# Atmega328P.net
KiCad netlist of a schematic drawn in Altium Designer
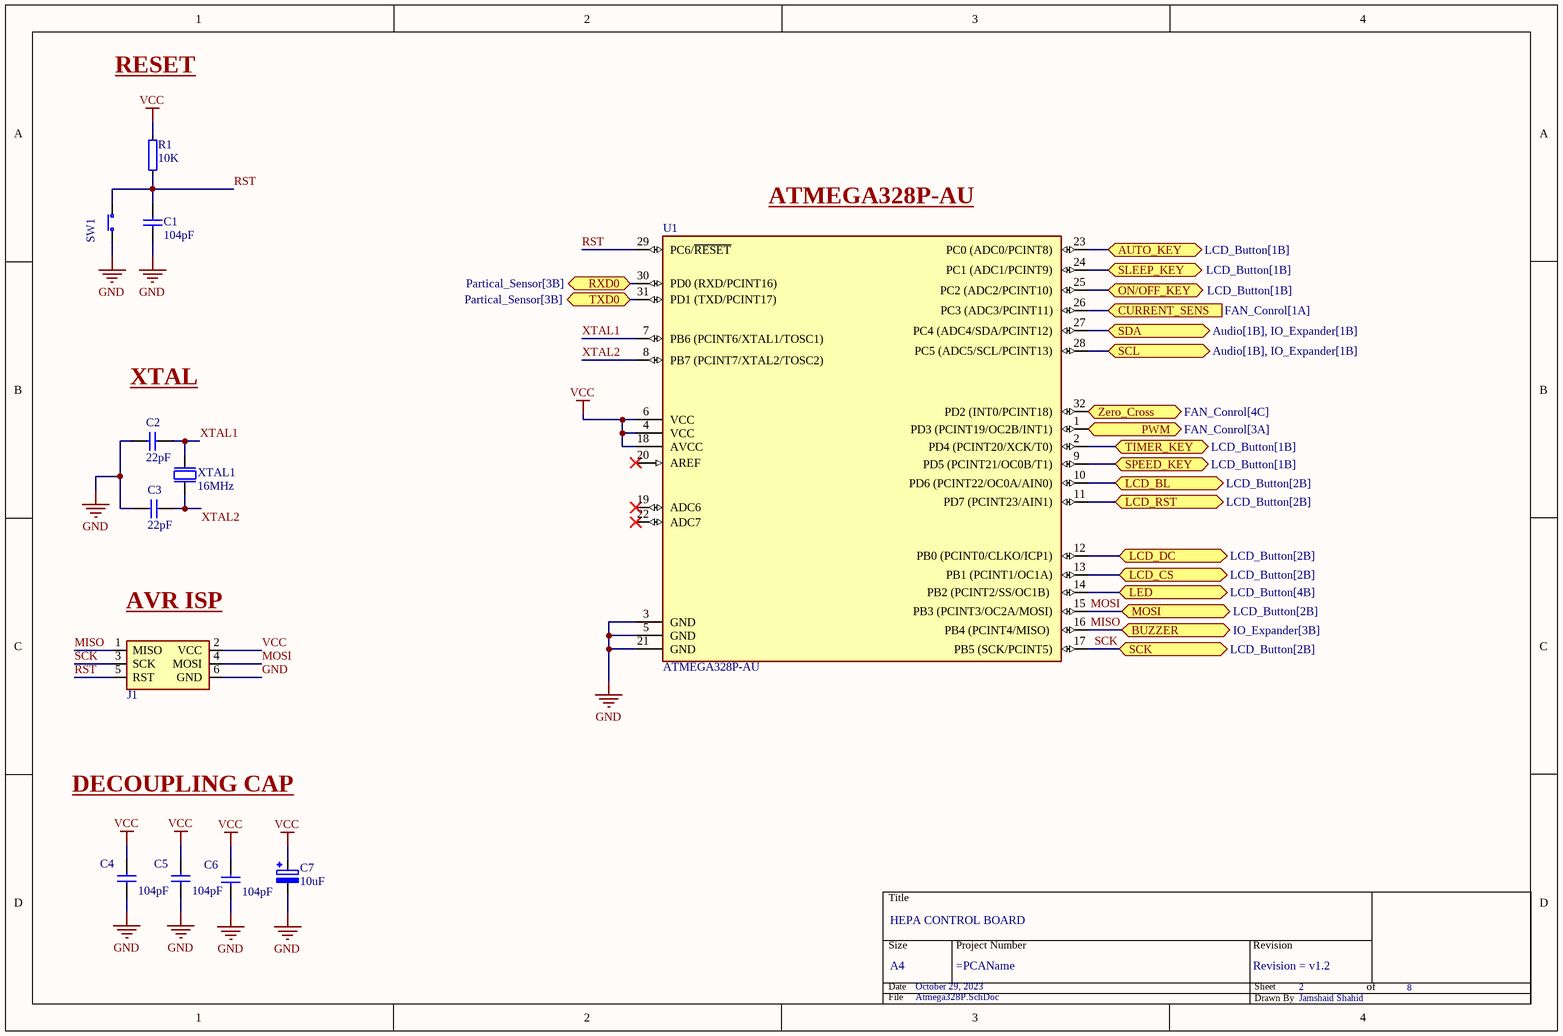
[diagram p0: Atmega328P.SchDoc]

(export (version "E")
  (design (tool "Eeschema 10.0.6"))
  (components
    (comp (ref "C1")
      (value "104pF")
      (footprint "CAPC2012X140N")
      (fields (field (name "PART NUMBER") "CAP_0805") (field (name "PUBLISHER") "Metal Circuits"))
      (libsource (lib "HEPA_LIB") (part "CAP_0805"))
    )
    (comp (ref "C2")
      (value "22pF")
      (footprint "CAPC2012X140N")
      (fields (field (name "PART NUMBER") "CAP_0805") (field (name "PUBLISHER") "Metal Circuits"))
      (libsource (lib "HEPA_LIB") (part "CAP_0805"))
    )
    (comp (ref "C3")
      (value "22pF")
      (footprint "CAPC2012X140N")
      (fields (field (name "PART NUMBER") "CAP_0805") (field (name "PUBLISHER") "Metal Circuits"))
      (libsource (lib "HEPA_LIB") (part "CAP_0805"))
    )
    (comp (ref "C4")
      (value "104pF")
      (footprint "CAPC2012X140N")
      (fields (field (name "PART NUMBER") "CAP_0805") (field (name "PUBLISHER") "Metal Circuits"))
      (libsource (lib "HEPA_LIB") (part "CAP_0805"))
    )
    (comp (ref "C5")
      (value "104pF")
      (footprint "CAPC2012X140N")
      (fields (field (name "PART NUMBER") "CAP_0805") (field (name "PUBLISHER") "Metal Circuits"))
      (libsource (lib "HEPA_LIB") (part "CAP_0805"))
    )
    (comp (ref "C6")
      (value "104pF")
      (footprint "CAPC2012X140N")
      (fields (field (name "PART NUMBER") "CAP_0805") (field (name "PUBLISHER") "Metal Circuits"))
      (libsource (lib "HEPA_LIB") (part "CAP_0805"))
    )
    (comp (ref "C7")
      (value "10uF")
      (footprint "CAPPRD250W50D630H1250")
      (description "Ø6.3 x 11mm LS=2.5mm Radial Aluminum Electrolytic Cap")
      (fields (field (name "PART NUMBER") "Cap Electrolytic") (field (name "PUBLISHER") "Metal Circuits"))
      (libsource (lib "HEPA_LIB") (part "Electrolytic Capacitor 6.3mm"))
    )
    (comp (ref "J1")
      (value "AVRISP Header")
      (footprint "AVRISP_Header")
      (description "AVR ISP Programming 2x3 Header male 2.54mm pith")
      (fields
        (field (name "PART NUMBER") "67997-206HLF")
        (field (name "MANUFACTURER") "Amphenol ICC (FCI)")
        (field (name "PUBLISHER") "Metal Circuits")
      )
      (libsource (lib "HEPA_LIB") (part "67997-206HLF"))
    )
    (comp (ref "R1")
      (value "10K")
      (footprint "RESC2012X65N")
      (description "RES SMD 1% 1/10W 0805")
      (fields (field (name "PART NUMBER") "RES_0805") (field (name "PUBLISHER") "Metal Circuits"))
      (libsource (lib "HEPA_LIB") (part "RES_0805"))
    )
    (comp (ref "SW1")
      (value "~")
      (footprint "SW_TL1105F160Q")
      (description "Tactile Switch, SPNO, Through Hole")
      (fields (field (name "PART NUMBER") "SW-PB") (field (name "PUBLISHER") "Metal Circuits"))
      (libsource (lib "HEPA_LIB") (part "SW-PB"))
    )
    (comp (ref "U1")
      (value "ATMEGA328P-AU")
      (footprint "QFP80P900X900X120-32N")
      (description "AVR AVR® ATmega Microcontroller IC 8-Bit 20MHz 32KB (16K x 16) FLASH 32-TQFP (7x7)")
      (fields
        (field (name "MANUFACTURER") "Microchip Technology")
        (field (name "PUBLISHER") "Metal Circuits")
      )
      (libsource (lib "HEPA_LIB") (part "ATMEGA328P-AU"))
    )
    (comp (ref "XTAL1")
      (value "16MHz")
      (footprint "XTAL_ECS-160-20-16X")
      (description "16 MHz ±30ppm Crystal 20pF 150 Ohms HC-49/US")
      (fields
        (field (name "PART NUMBER") "ECS-40-20-4")
        (field (name "MANUFACTURER") "ECS Inc.")
        (field (name "PUBLISHER") "Metal Circuits")
      )
      (libsource (lib "HEPA_LIB") (part "ECS-40-20-4"))
    )
  )
  (nets
    (net (code "1") (name "/AUTO_KEY") (class "Default")
      (node (ref "U1") (pin "23") (pinfunction "PC0_(ADC0/PCINT8)_23") (pintype "bidirectional"))
    )
    (net (code "2") (name "/CURRENT_SENS") (class "Default")
      (node (ref "U1") (pin "26") (pinfunction "PC3_(ADC3/PCINT11)_26") (pintype "bidirectional"))
    )
    (net (code "3") (name "/LCD_BL") (class "Default")
      (node (ref "U1") (pin "10") (pinfunction "PD6_(PCINT22/OC0A/AIN0)_10") (pintype "bidirectional"))
    )
    (net (code "4") (name "/LCD_CS") (class "Default")
      (node (ref "U1") (pin "13") (pinfunction "PB1_(PCINT1/OC1A)_13") (pintype "bidirectional"))
    )
    (net (code "5") (name "/LCD_DC") (class "Default")
      (node (ref "U1") (pin "12") (pinfunction "PB0_(PCINT0/CLKO/ICP1)_12") (pintype "bidirectional"))
    )
    (net (code "6") (name "/LCD_RST") (class "Default")
      (node (ref "U1") (pin "11") (pinfunction "PD7_(PCINT23/AIN1)_11") (pintype "bidirectional"))
    )
    (net (code "7") (name "/LED") (class "Default")
      (node (ref "U1") (pin "14") (pinfunction "PB2_(PCINT2/SS/OC1B)_14") (pintype "bidirectional"))
    )
    (net (code "8") (name "/MISO") (class "Default")
      (node (ref "J1") (pin "1") (pinfunction "MISO_1") (pintype "passive"))
      (node (ref "U1") (pin "16") (pinfunction "PB4_(PCINT4/MISO)_16") (pintype "bidirectional"))
    )
    (net (code "9") (name "/MOSI") (class "Default")
      (node (ref "J1") (pin "4") (pinfunction "MOSI_4") (pintype "passive"))
      (node (ref "U1") (pin "15") (pinfunction "PB3_(PCINT3/OC2A/MOSI)_15") (pintype "bidirectional"))
    )
    (net (code "10") (name "/ON{slash}OFF_KEY") (class "Default")
      (node (ref "U1") (pin "25") (pinfunction "PC2_(ADC2/PCINT10)_25") (pintype "bidirectional"))
    )
    (net (code "11") (name "/PWM") (class "Default")
      (node (ref "U1") (pin "1") (pinfunction "PD3_(PCINT19/OC2B/INT1)_1") (pintype "bidirectional"))
    )
    (net (code "12") (name "/RST") (class "Default")
      (node (ref "C1") (pin "2") (pinfunction "2_2") (pintype "passive"))
      (node (ref "J1") (pin "5") (pinfunction "RST_5") (pintype "passive"))
      (node (ref "R1") (pin "1") (pinfunction "1_1") (pintype "passive"))
      (node (ref "SW1") (pin "1") (pinfunction "N.O_1") (pintype "passive"))
      (node (ref "U1") (pin "29") (pinfunction "PC6/~{RESET}_29") (pintype "bidirectional"))
    )
    (net (code "13") (name "/RXD0") (class "Default")
      (node (ref "U1") (pin "30") (pinfunction "PD0_(RXD/PCINT16)_30") (pintype "bidirectional"))
    )
    (net (code "14") (name "/SCK") (class "Default")
      (node (ref "J1") (pin "3") (pinfunction "SCK_3") (pintype "passive"))
      (node (ref "U1") (pin "17") (pinfunction "PB5_(SCK/PCINT5)_17") (pintype "bidirectional"))
    )
    (net (code "15") (name "/SCL") (class "Default")
      (node (ref "U1") (pin "28") (pinfunction "PC5_(ADC5/SCL/PCINT13)_28") (pintype "bidirectional"))
    )
    (net (code "16") (name "/SDA") (class "Default")
      (node (ref "U1") (pin "27") (pinfunction "PC4_(ADC4/SDA/PCINT12)_27") (pintype "bidirectional"))
    )
    (net (code "17") (name "/SLEEP_KEY") (class "Default")
      (node (ref "U1") (pin "24") (pinfunction "PC1_(ADC1/PCINT9)_24") (pintype "bidirectional"))
    )
    (net (code "18") (name "/SPEED_KEY") (class "Default")
      (node (ref "U1") (pin "9") (pinfunction "PD5_(PCINT21/OC0B/T1)_9") (pintype "bidirectional"))
    )
    (net (code "19") (name "/TIMER_KEY") (class "Default")
      (node (ref "U1") (pin "2") (pinfunction "PD4_(PCINT20/XCK/T0)_2") (pintype "bidirectional"))
    )
    (net (code "20") (name "/TXD0") (class "Default")
      (node (ref "U1") (pin "31") (pinfunction "PD1_(TXD/PCINT17)_31") (pintype "bidirectional"))
    )
    (net (code "21") (name "/XTAL1") (class "Default")
      (node (ref "C2") (pin "2") (pinfunction "2_2") (pintype "passive"))
      (node (ref "U1") (pin "7") (pinfunction "PB6_(PCINT6/XTAL1/TOSC1)_7") (pintype "bidirectional"))
      (node (ref "XTAL1") (pin "2") (pinfunction "out_2") (pintype "passive"))
    )
    (net (code "22") (name "/XTAL2") (class "Default")
      (node (ref "C3") (pin "2") (pinfunction "2_2") (pintype "passive"))
      (node (ref "U1") (pin "8") (pinfunction "PB7_(PCINT7/XTAL2/TOSC2)_8") (pintype "bidirectional"))
      (node (ref "XTAL1") (pin "1") (pinfunction "inp_1") (pintype "passive"))
    )
    (net (code "23") (name "/Zero_Cross") (class "Default")
      (node (ref "U1") (pin "32") (pinfunction "PD2_(INT0/PCINT18)_32") (pintype "bidirectional"))
    )
    (net (code "24") (name "GND") (class "Default")
      (node (ref "C1") (pin "1") (pinfunction "1_1") (pintype "passive"))
      (node (ref "C2") (pin "1") (pinfunction "1_1") (pintype "passive"))
      (node (ref "C3") (pin "1") (pinfunction "1_1") (pintype "passive"))
      (node (ref "C4") (pin "1") (pinfunction "1_1") (pintype "passive"))
      (node (ref "C5") (pin "1") (pinfunction "1_1") (pintype "passive"))
      (node (ref "C6") (pin "1") (pinfunction "1_1") (pintype "passive"))
      (node (ref "C7") (pin "2") (pinfunction "2_2") (pintype "passive"))
      (node (ref "J1") (pin "6") (pinfunction "GND_6") (pintype "passive"))
      (node (ref "SW1") (pin "2") (pinfunction "COM_2") (pintype "passive"))
      (node (ref "U1") (pin "21") (pinfunction "GND_21") (pintype "power_in"))
      (node (ref "U1") (pin "3") (pinfunction "GND_3") (pintype "power_in"))
      (node (ref "U1") (pin "5") (pinfunction "GND_5") (pintype "power_in"))
    )
    (net (code "25") (name "VCC") (class "Default")
      (node (ref "C4") (pin "2") (pinfunction "2_2") (pintype "passive"))
      (node (ref "C5") (pin "2") (pinfunction "2_2") (pintype "passive"))
      (node (ref "C6") (pin "2") (pinfunction "2_2") (pintype "passive"))
      (node (ref "C7") (pin "1") (pinfunction "1_1") (pintype "passive"))
      (node (ref "J1") (pin "2") (pinfunction "VCC_2") (pintype "passive"))
      (node (ref "R1") (pin "2") (pinfunction "2_2") (pintype "passive"))
      (node (ref "U1") (pin "18") (pinfunction "AVCC_18") (pintype "power_in"))
      (node (ref "U1") (pin "4") (pinfunction "VCC_4") (pintype "power_in"))
      (node (ref "U1") (pin "6") (pinfunction "VCC_6") (pintype "power_in"))
    )
    (net (code "26") (name "unconnected-(U1-ADC6-Pad19)") (class "Default")
      (node (ref "U1") (pin "19") (pinfunction "ADC6_19") (pintype "bidirectional+no_connect"))
    )
    (net (code "27") (name "unconnected-(U1-ADC7-Pad22)") (class "Default")
      (node (ref "U1") (pin "22") (pinfunction "ADC7_22") (pintype "bidirectional+no_connect"))
    )
    (net (code "28") (name "unconnected-(U1-AREF-Pad20)") (class "Default")
      (node (ref "U1") (pin "20") (pinfunction "AREF_20") (pintype "input+no_connect"))
    )
  )
)
